# msq_ethrottle_soic.net
KiCad netlist of a schematic drawn in EasyEDA Pro
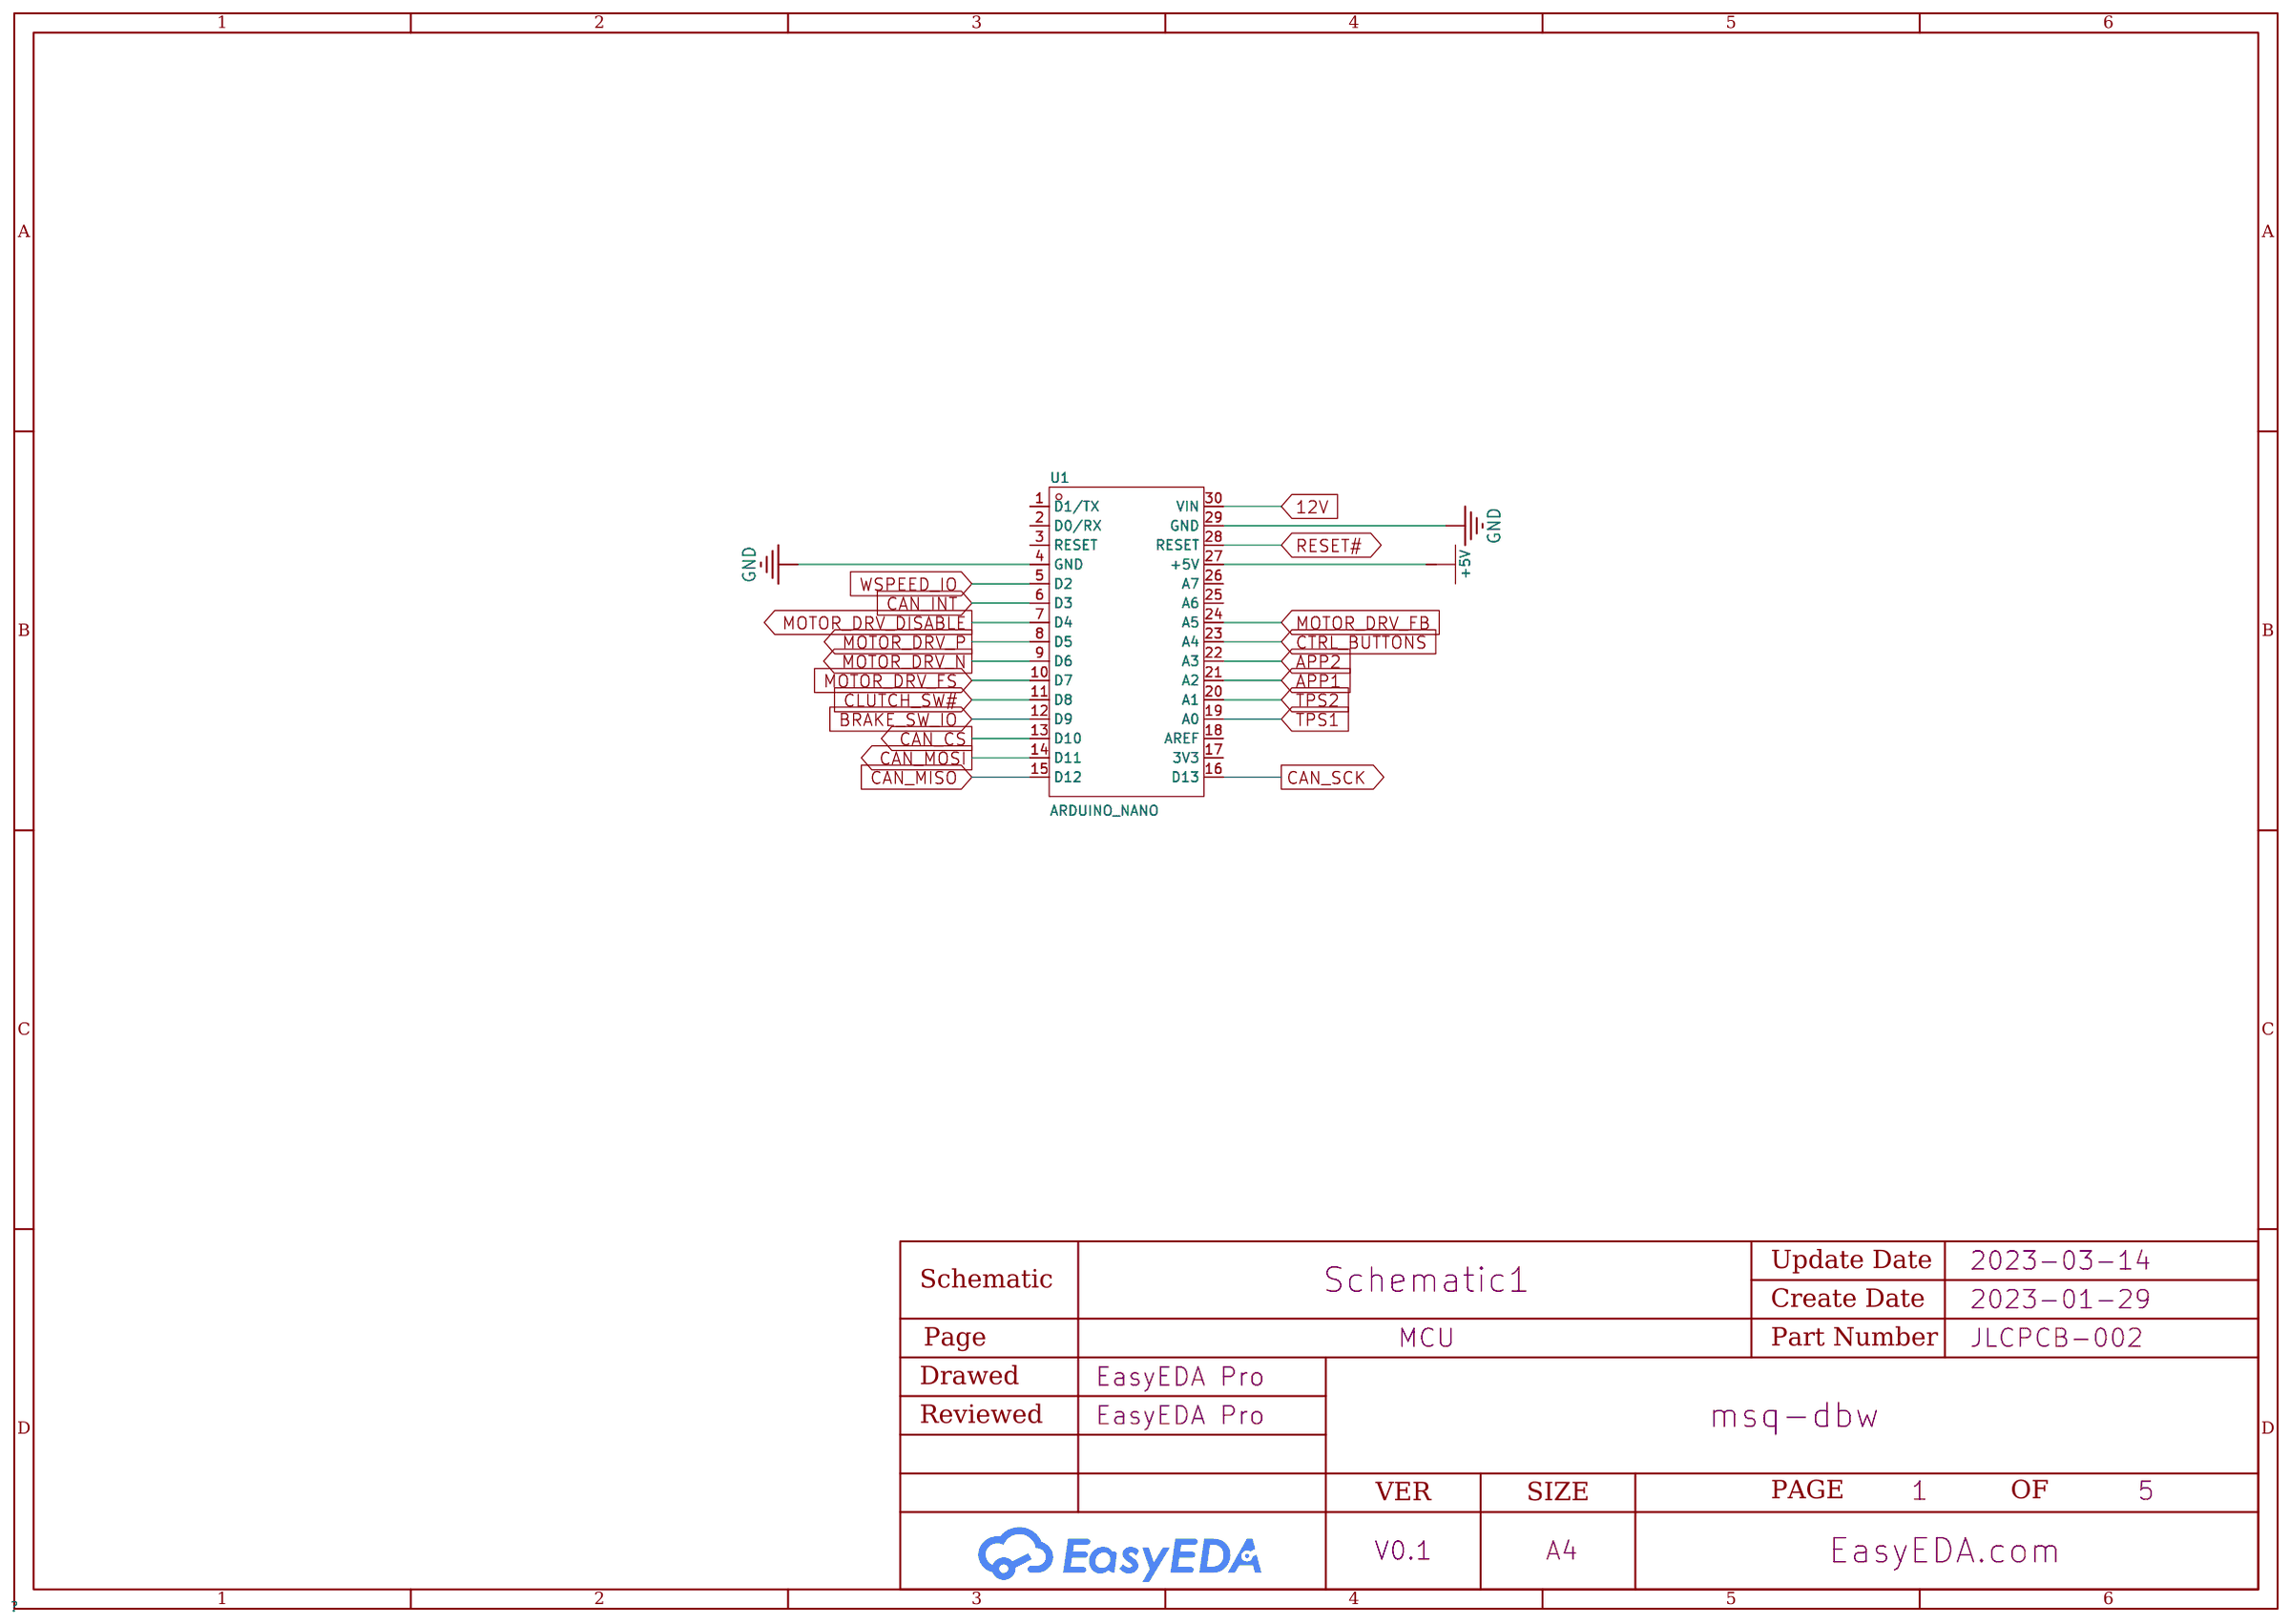
[diagram p0: MCU]
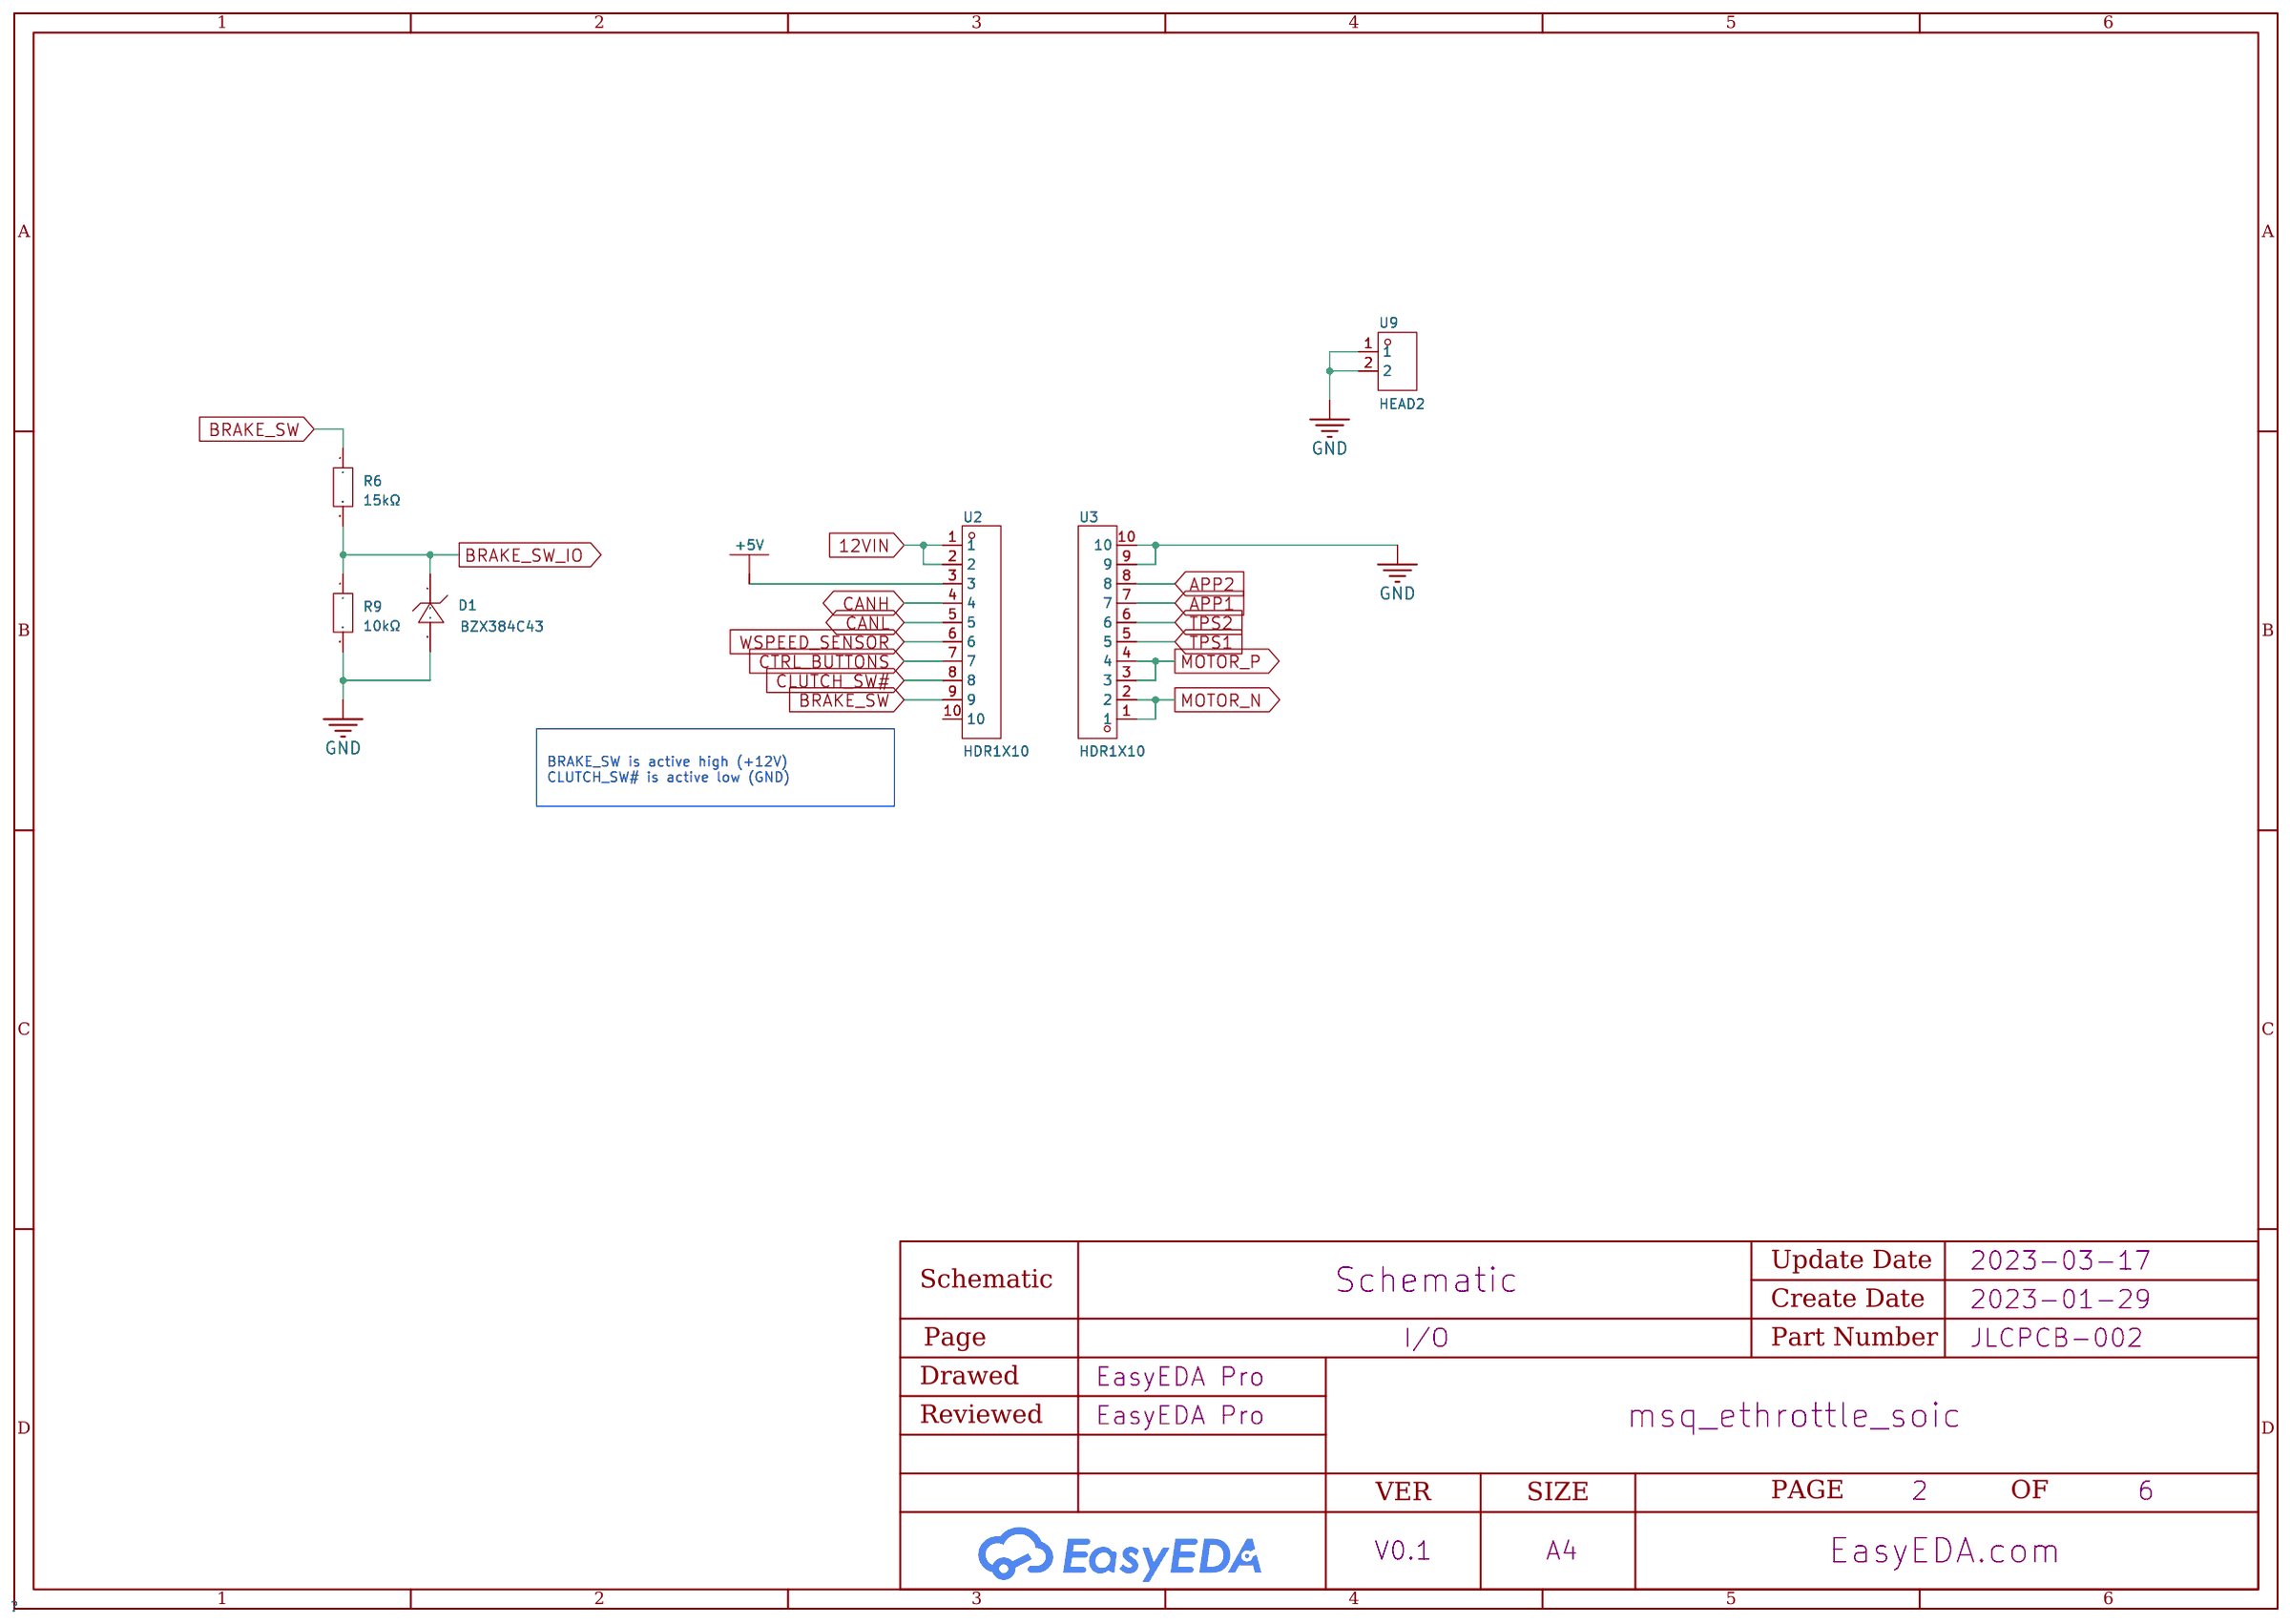
[diagram p1: I/O]
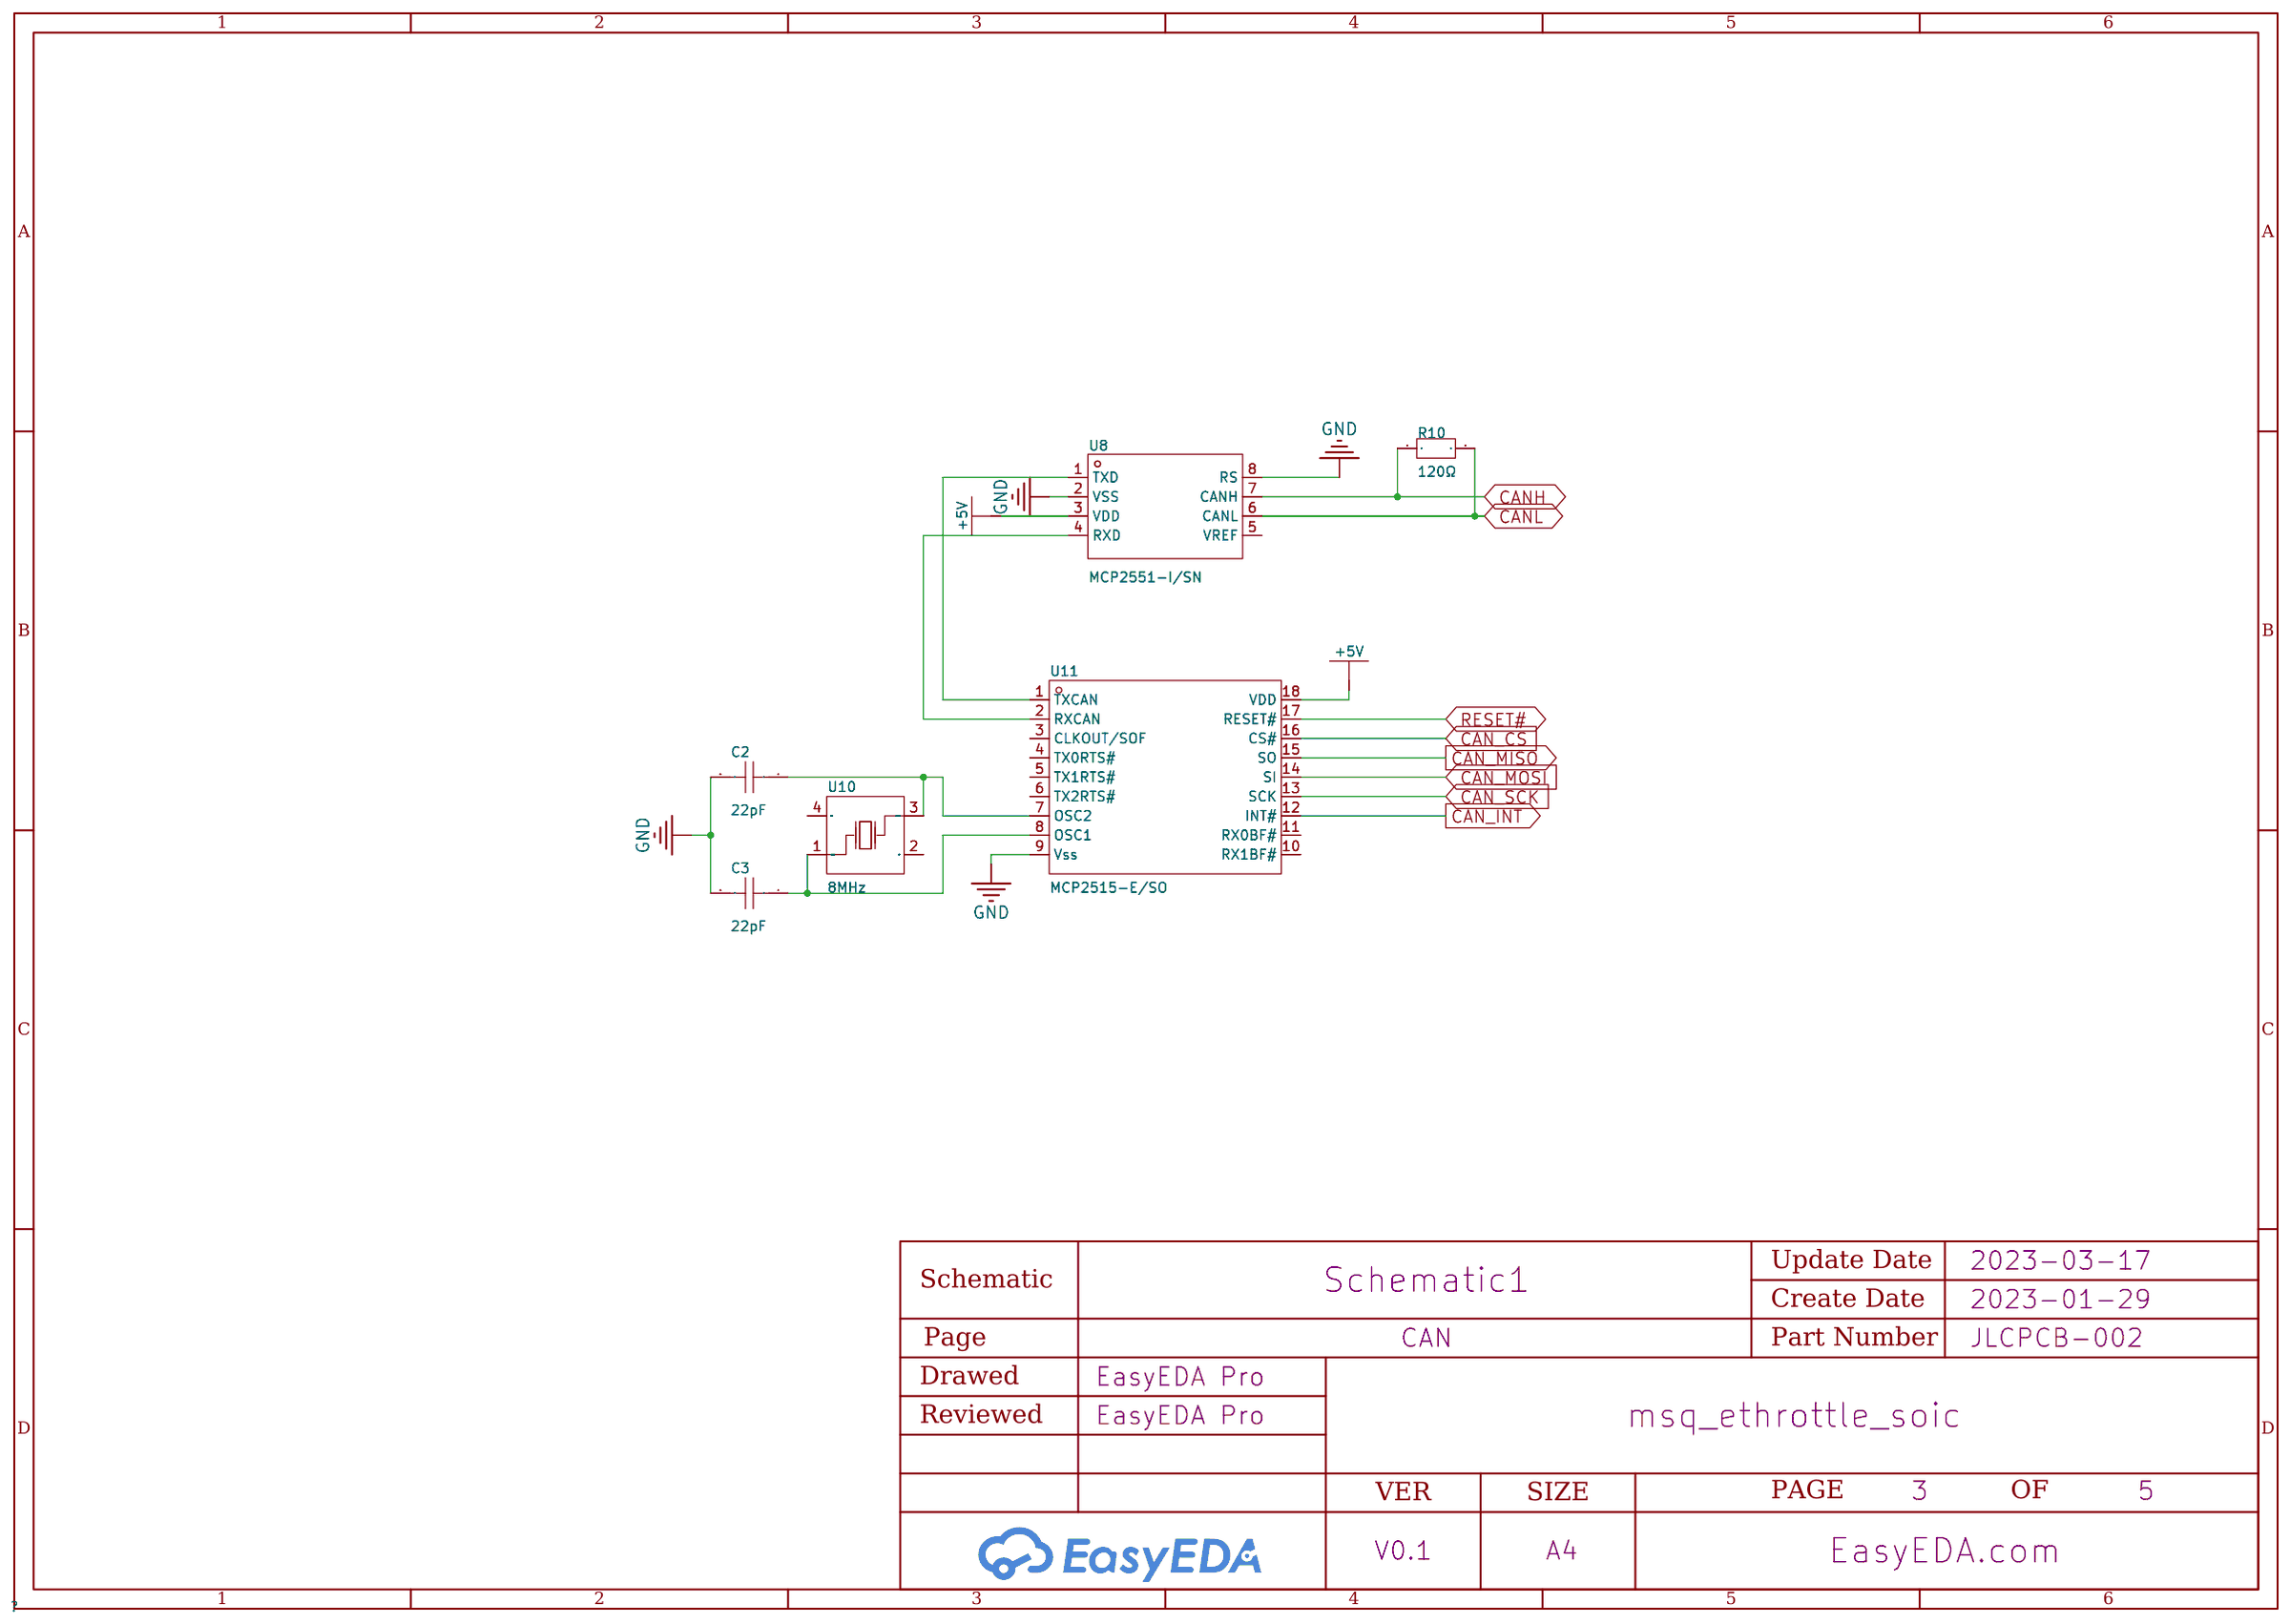
[diagram p2: CAN]
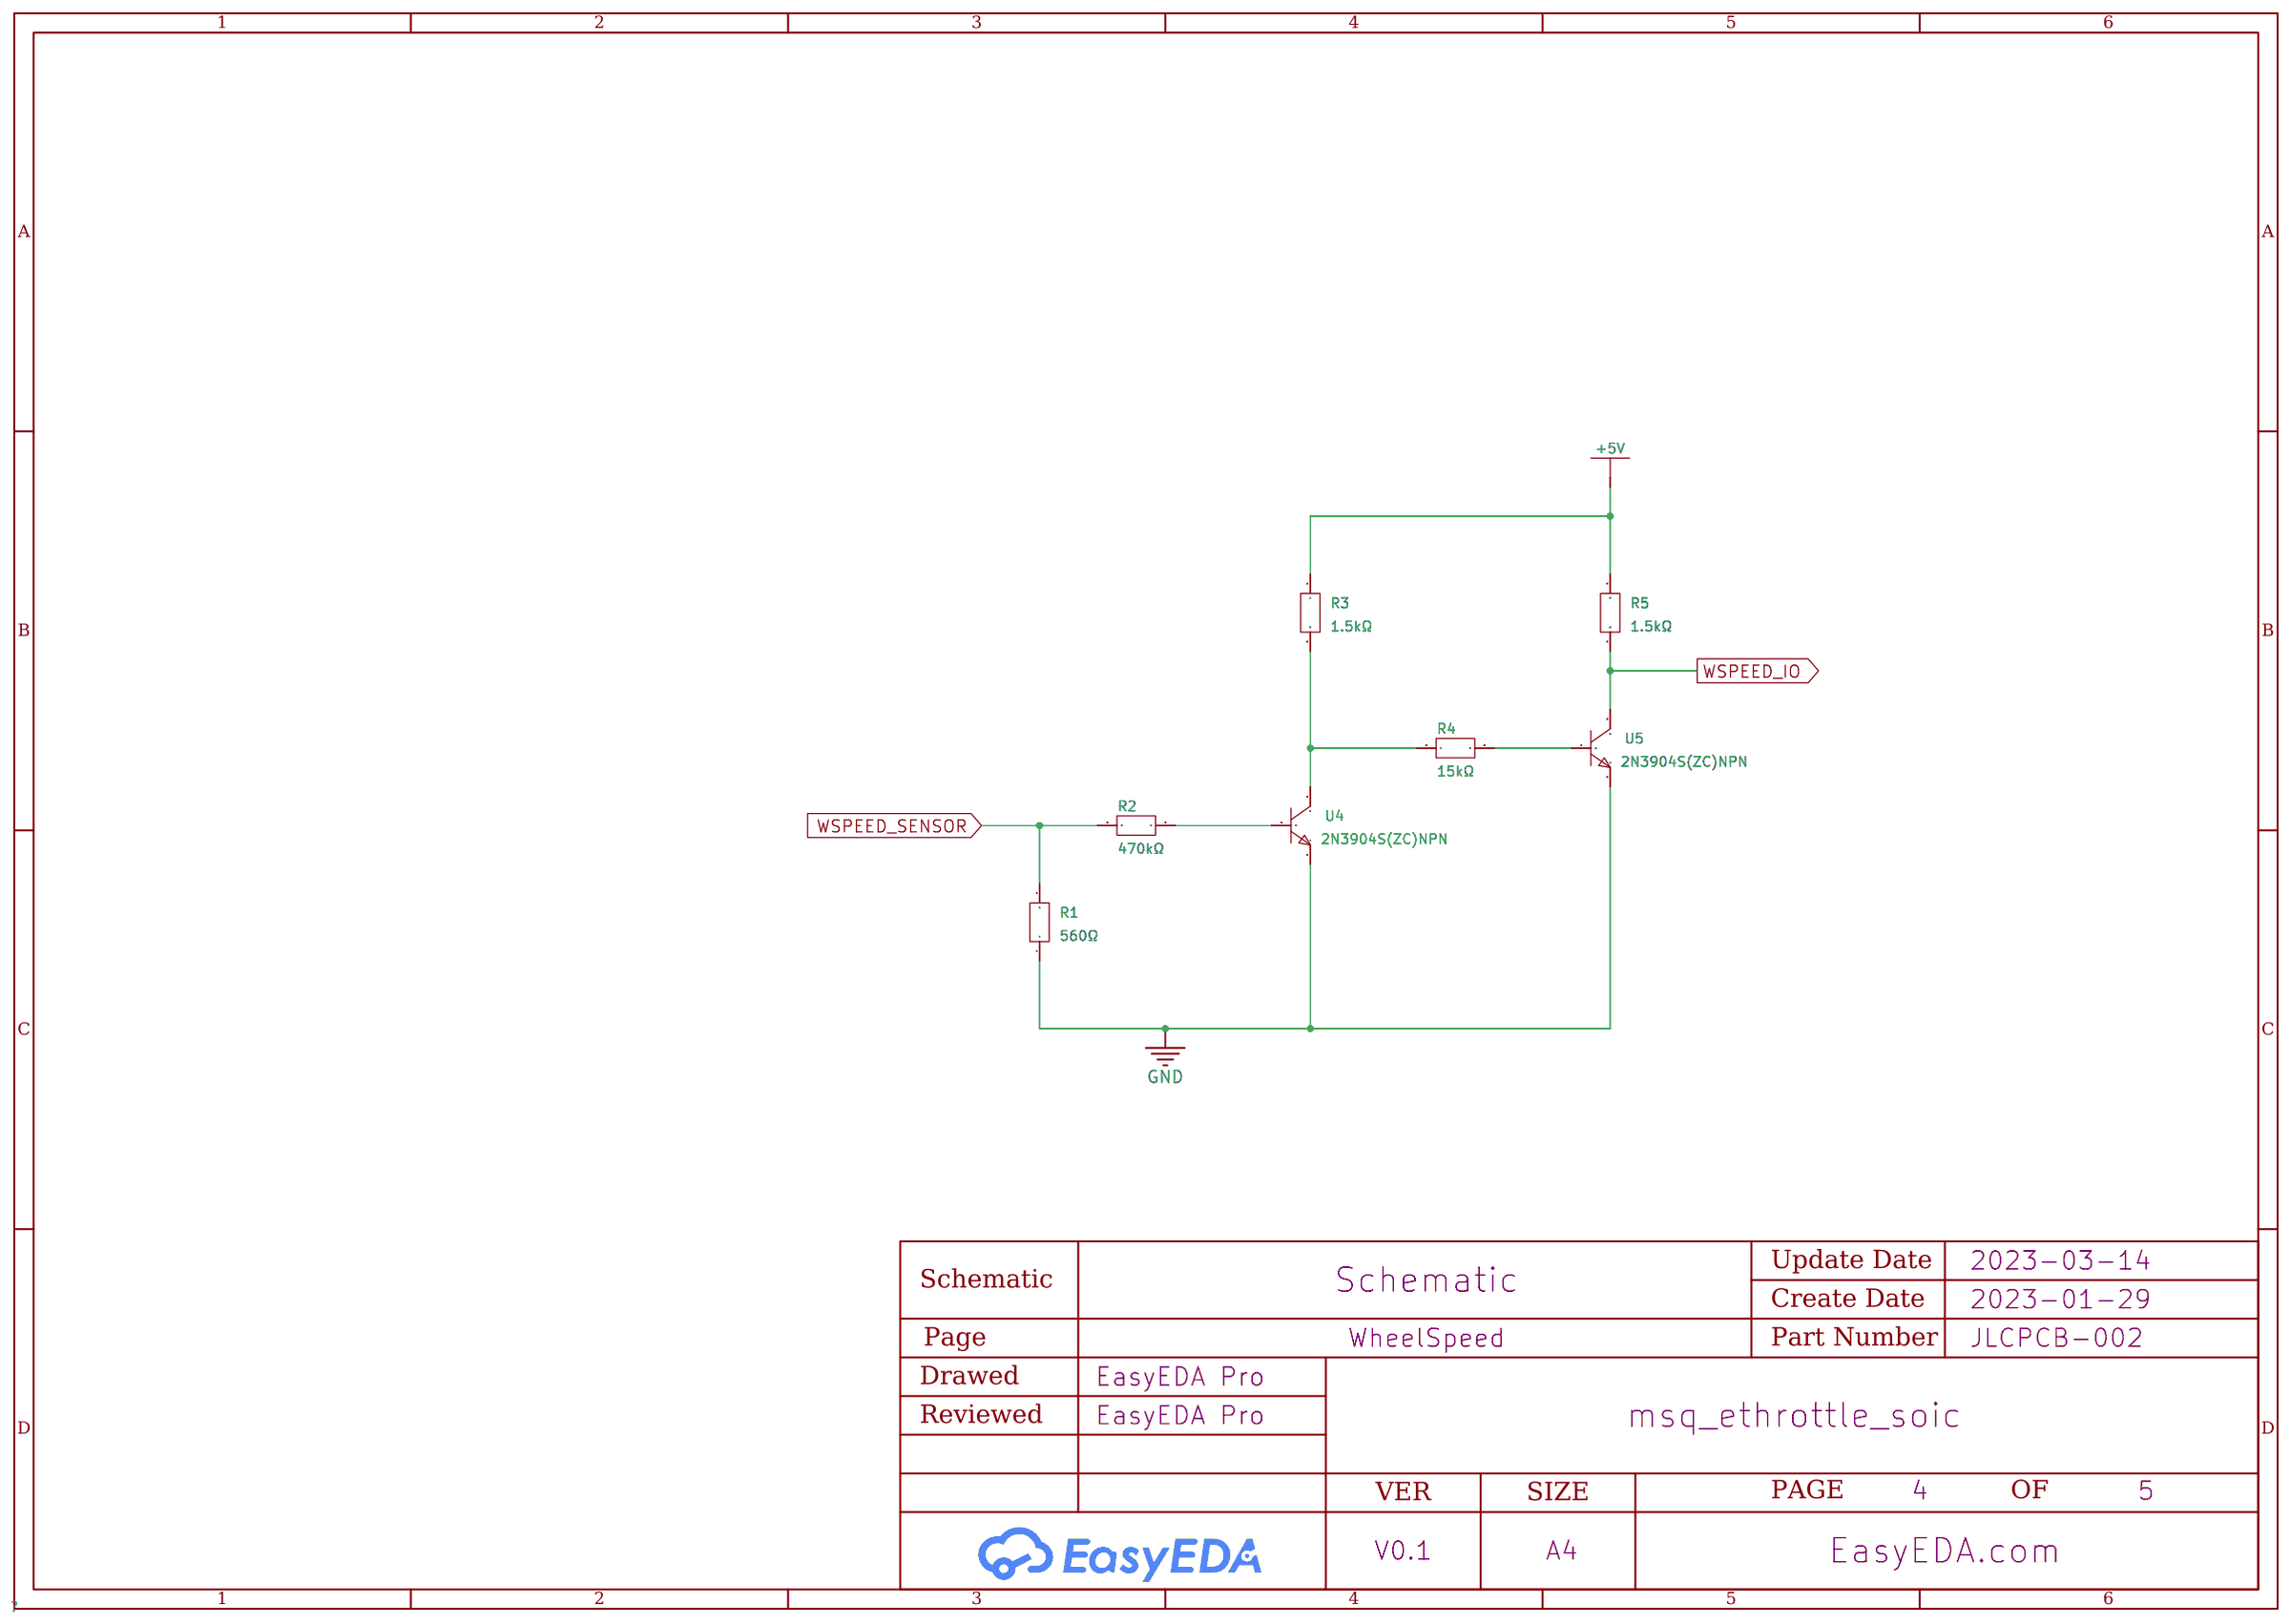
[diagram p3: WheelSpeed]
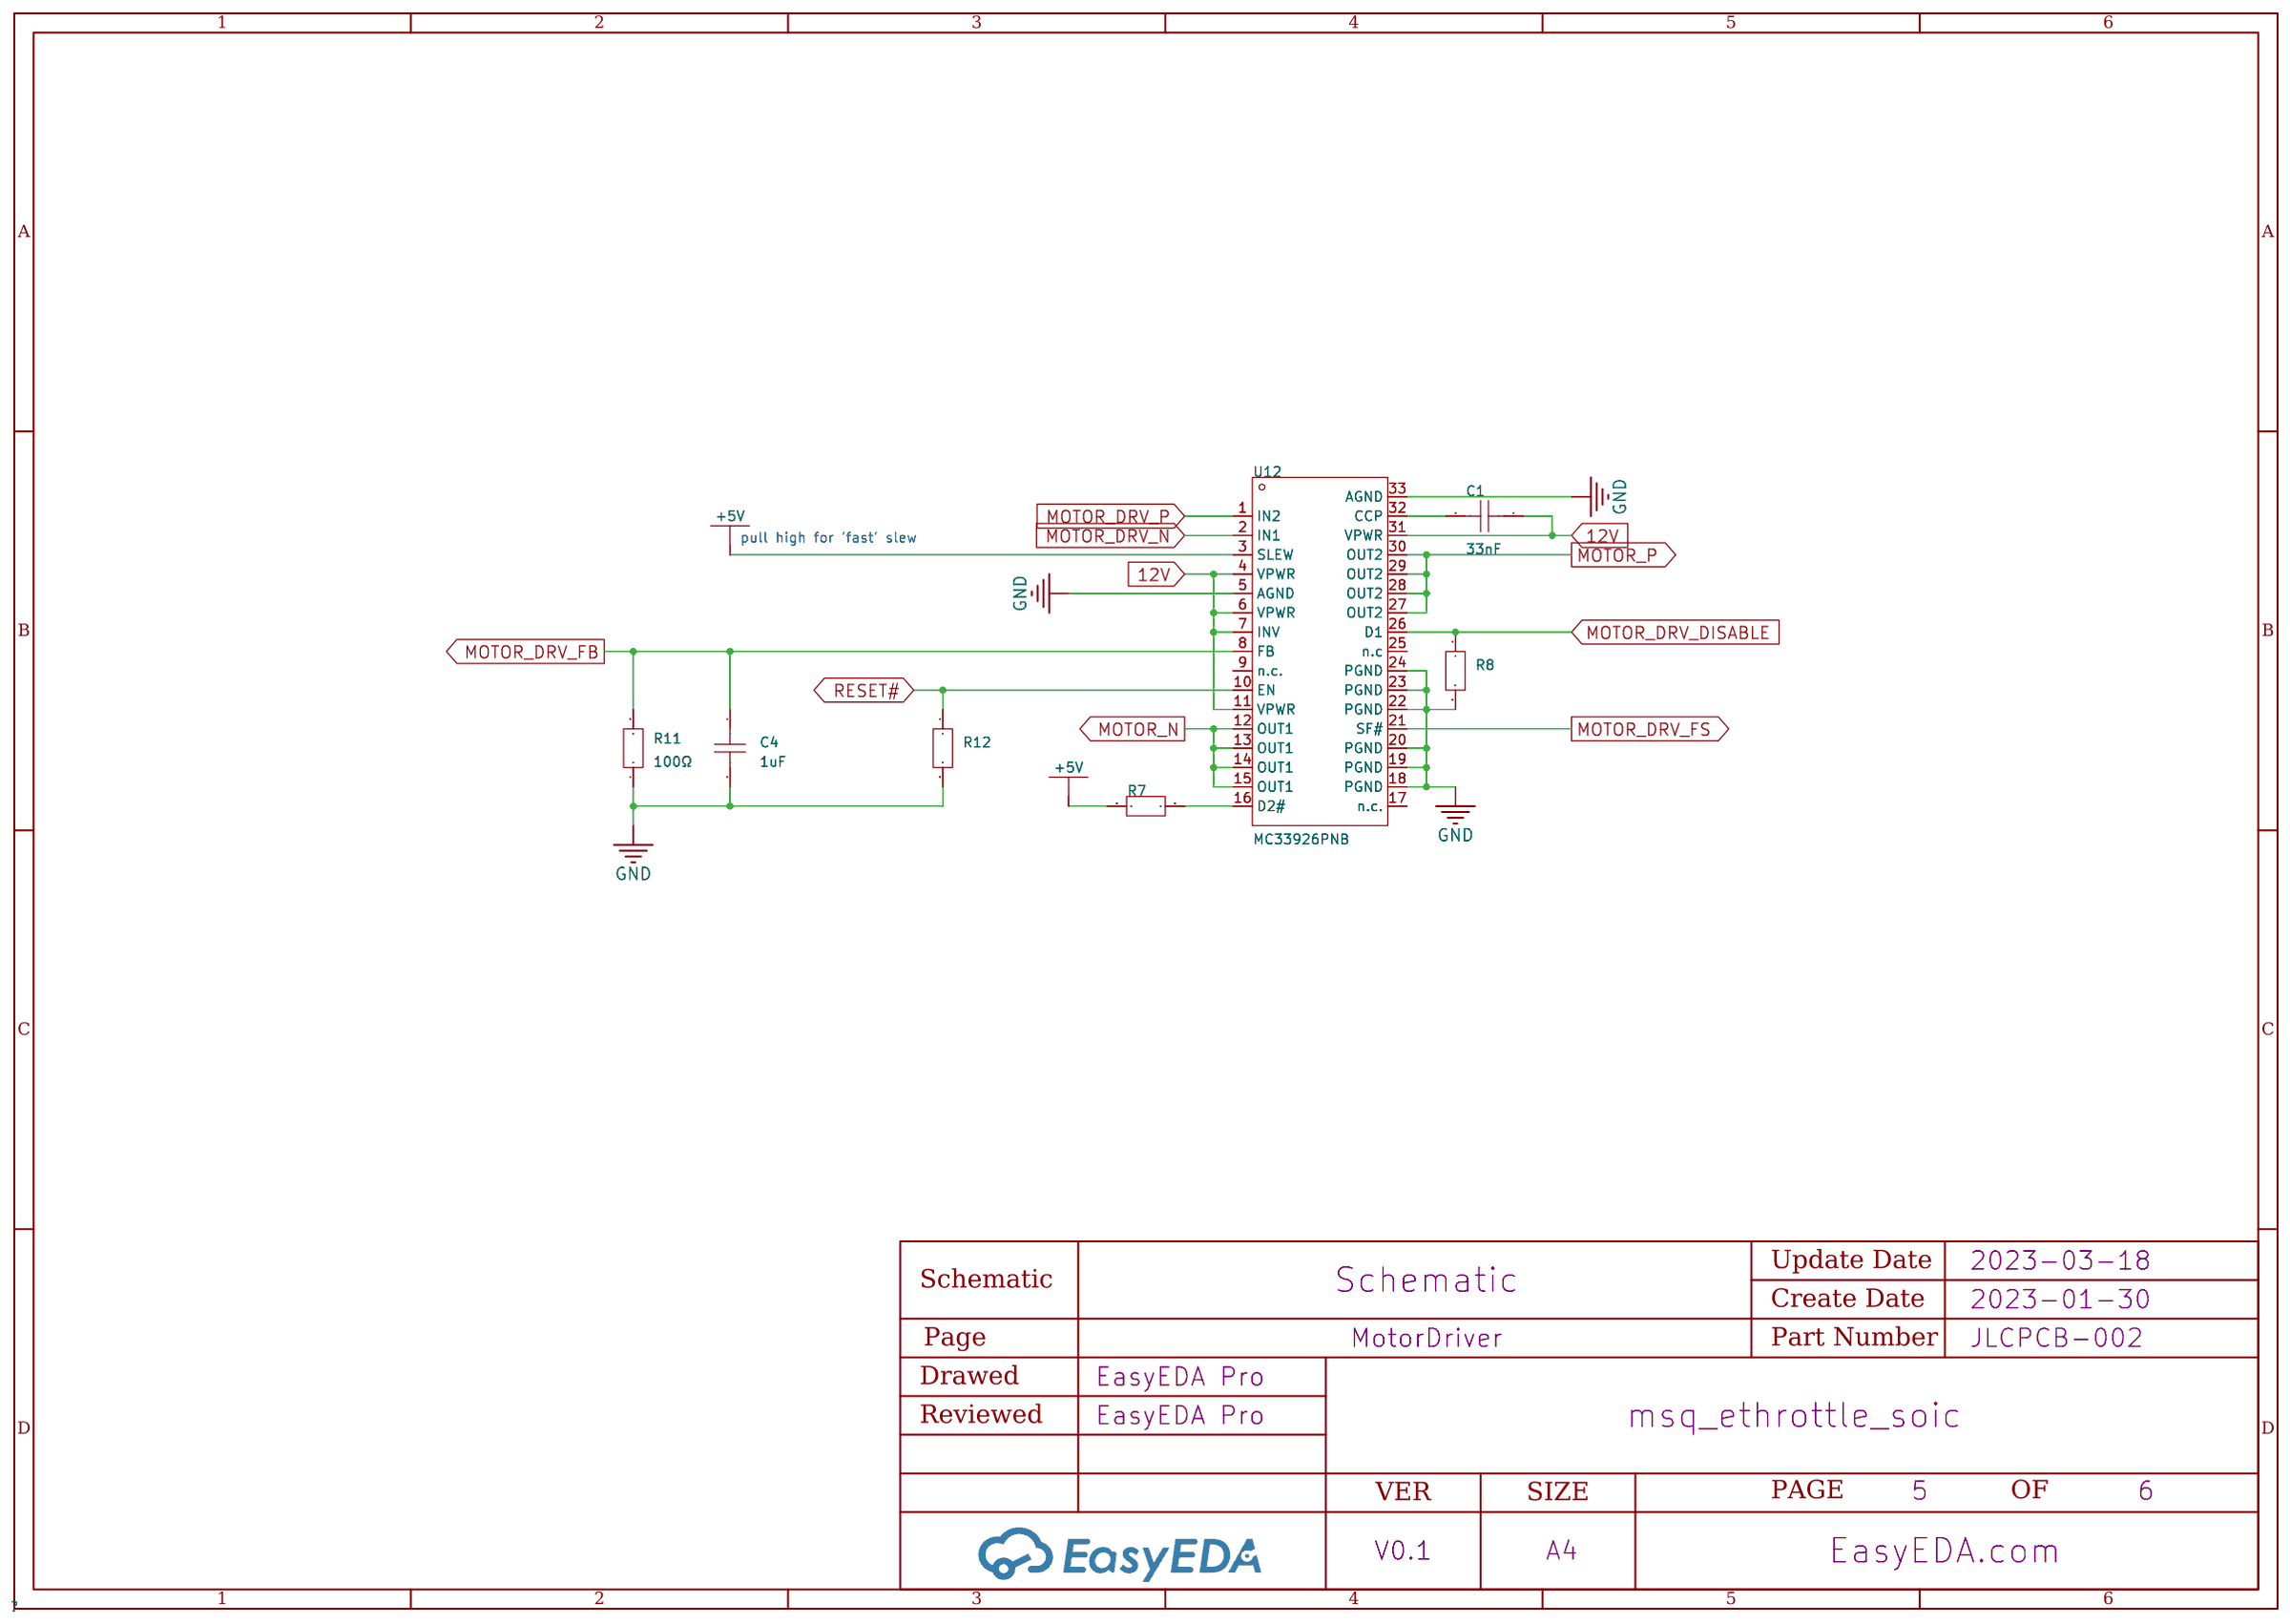
[diagram p4: MotorDriver]
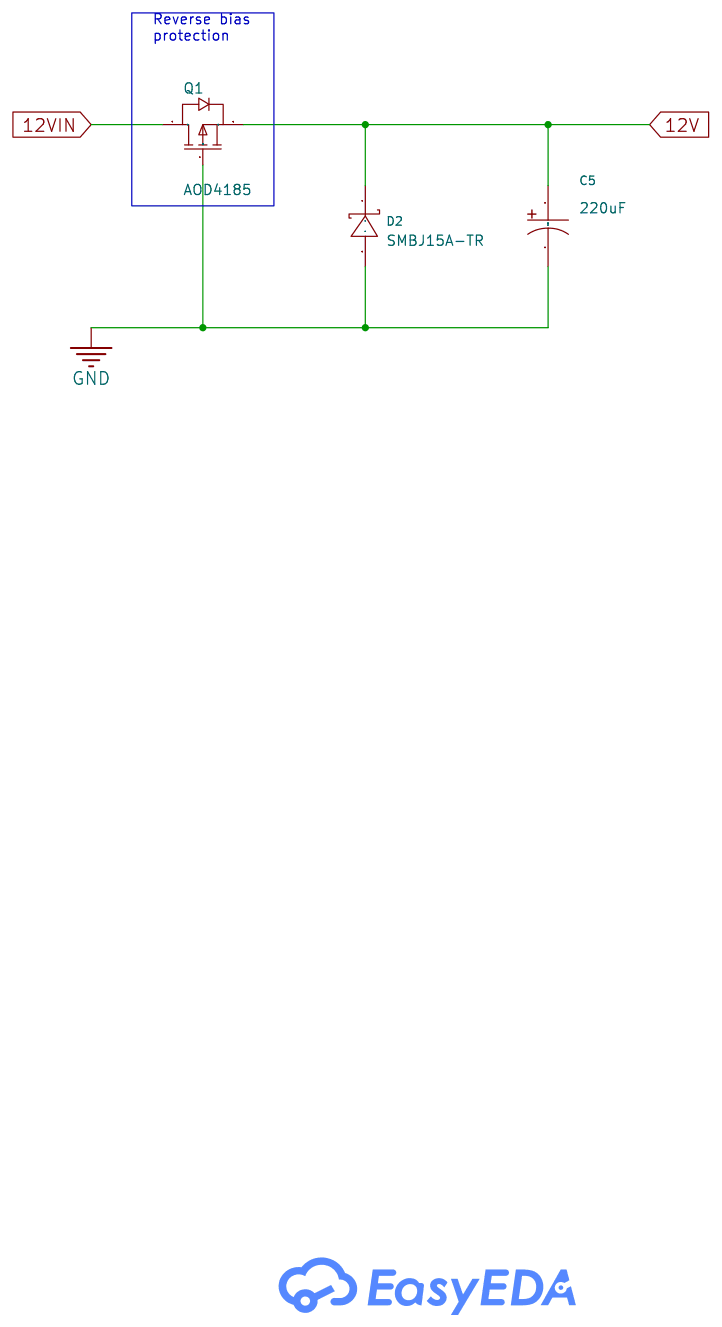
[diagram p5: Power]

(export (version "E")
  (design (tool "Eeschema 10.0.6"))
  (components
    (comp (ref "U1")
      (value "ARDUINO_NANO")
      (footprint "easyedapro:COMM-TH_ARDUINO_NANO")
      (libsource (lib "easyedapro") (part "ARDUINO_NANO"))
    )
    (comp (ref "D1")
      (value "BZX384C43")
      (footprint "easyedapro:SOD-323_L1.7-W1.3-LS2.6-RD")
      (fields (field (name "Manufacturer") "EIC"))
      (libsource (lib "easyedapro") (part "BZX384C43"))
    )
    (comp (ref "R6")
      (value "15kΩ")
      (footprint "easyedapro:R0805")
      (fields
        (field (name "Manufacturer Part") "0603WAF1002T5E")
        (field (name "Manufacturer") "UNI-ROYAL(厚声)")
      )
      (libsource (lib "easyedapro") (part "RT0805BRD07360RL"))
    )
    (comp (ref "R9")
      (value "10kΩ")
      (footprint "easyedapro:R0805")
      (fields
        (field (name "Manufacturer Part") "0603WAF1002T5E")
        (field (name "Manufacturer") "UNI-ROYAL(厚声)")
      )
      (libsource (lib "easyedapro") (part "RT0805BRD07360RL"))
    )
    (comp (ref "U2")
      (value "HDR1X10")
      (footprint "easyedapro:HDR-TH_10P-P2.54-V-F_C9900008052")
      (libsource (lib "easyedapro") (part "HDR1X10"))
    )
    (comp (ref "U3")
      (value "HDR1X10")
      (footprint "easyedapro:HDR-TH_10P-P2.54-V-F_C9900008052")
      (libsource (lib "easyedapro") (part "HDR1X10"))
    )
    (comp (ref "U9")
      (value "HEAD2")
      (footprint "easyedapro:HDR-TH_2P-P2.54-V-M")
      (libsource (lib "easyedapro") (part "HEAD2"))
    )
    (comp (ref "C2")
      (value "22pF")
      (footprint "easyedapro:C0603")
      (libsource (lib "easyedapro") (part "CAP"))
    )
    (comp (ref "C3")
      (value "22pF")
      (footprint "easyedapro:C0603")
      (libsource (lib "easyedapro") (part "CAP"))
    )
    (comp (ref "R10")
      (value "120Ω")
      (footprint "easyedapro:R0805")
      (fields
        (field (name "Manufacturer Part") "0603WAF1002T5E")
        (field (name "Manufacturer") "UNI-ROYAL(厚声)")
        (field (name "Tolerance") "±1%")
      )
      (libsource (lib "easyedapro") (part "RT0805BRD07360RL"))
    )
    (comp (ref "U8")
      (value "MCP2551-I/SN")
      (footprint "easyedapro:SOIC-8_L4.9-W3.9-P1.27-LS6.0-BL")
      (description "Type:Transceiver Supply Voltage:4.5V~5.5V Supply Voltage:4.5V~5.5V")
      (fields (field (name "Manufacturer") "MICROCHIP(美国微芯)"))
      (libsource (lib "easyedapro") (part "MCP2551-I/SN"))
    )
    (comp (ref "U10")
      (value "8MHz")
      (footprint "easyedapro:CRYSTAL-SMD_4P-L3.2-W2.5-BL")
      (fields (field (name "Manufacturer Part") "L327S270S11L") (field (name "Manufacturer") "Lucki(蓝晶)"))
      (libsource (lib "easyedapro") (part "L327S270S11L"))
    )
    (comp (ref "U11")
      (value "MCP2515-E/SO")
      (footprint "easyedapro:SOIC-18_L11.6-W7.5-P1.27-LS10.3-BL")
      (fields (field (name "Manufacturer") "MICROCHIP(美国微芯)"))
      (libsource (lib "easyedapro") (part "MCP2515-E/SO"))
    )
    (comp (ref "R1")
      (value "560Ω")
      (footprint "easyedapro:R0805")
      (fields
        (field (name "Manufacturer Part") "0603WAF1002T5E")
        (field (name "Manufacturer") "UNI-ROYAL(厚声)")
        (field (name "Tolerance") "±1%")
      )
      (libsource (lib "easyedapro") (part "RT0805BRD07360RL"))
    )
    (comp (ref "R2")
      (value "470kΩ")
      (footprint "easyedapro:R0805")
      (fields
        (field (name "Manufacturer Part") "0603WAF1002T5E")
        (field (name "Manufacturer") "UNI-ROYAL(厚声)")
        (field (name "Tolerance") "±1%")
      )
      (libsource (lib "easyedapro") (part "RT0805BRD07360RL"))
    )
    (comp (ref "R3")
      (value "1.5kΩ")
      (footprint "easyedapro:R0805")
      (fields
        (field (name "Manufacturer Part") "0603WAF1002T5E")
        (field (name "Manufacturer") "UNI-ROYAL(厚声)")
        (field (name "Tolerance") "±1%")
      )
      (libsource (lib "easyedapro") (part "RT0805BRD07360RL"))
    )
    (comp (ref "R4")
      (value "15kΩ")
      (footprint "easyedapro:R0805")
      (fields
        (field (name "Manufacturer Part") "0603WAF1002T5E")
        (field (name "Manufacturer") "UNI-ROYAL(厚声)")
        (field (name "Tolerance") "±1%")
      )
      (libsource (lib "easyedapro") (part "RT0805BRD07360RL"))
    )
    (comp (ref "R5")
      (value "1.5kΩ")
      (footprint "easyedapro:R0805")
      (fields
        (field (name "Manufacturer Part") "0603WAF1002T5E")
        (field (name "Manufacturer") "UNI-ROYAL(厚声)")
        (field (name "Tolerance") "±1%")
      )
      (libsource (lib "easyedapro") (part "RT0805BRD07360RL"))
    )
    (comp (ref "U4")
      (value "2N3904S(ZC)NPN")
      (footprint "easyedapro:SOT-23-3_L2.9-W1.3-P0.95-LS2.4-BR")
      (libsource (lib "easyedapro") (part "2N3904S(ZC)NPN"))
    )
    (comp (ref "U5")
      (value "2N3904S(ZC)NPN")
      (footprint "easyedapro:SOT-23-3_L2.9-W1.3-P0.95-LS2.4-BR")
      (libsource (lib "easyedapro") (part "2N3904S(ZC)NPN"))
    )
    (comp (ref "C1")
      (value "33nF")
      (footprint "easyedapro:C0603")
      (libsource (lib "easyedapro") (part "CAP"))
    )
    (comp (ref "C4") (value "1uF") (footprint "easyedapro:C0603") (libsource (lib "easyedapro") (part "CAP")))
    (comp (ref "R7")
      (value "10kΩ")
      (footprint "easyedapro:R0805")
      (fields
        (field (name "Manufacturer Part") "0603WAF1002T5E")
        (field (name "Manufacturer") "UNI-ROYAL(厚声)")
      )
      (libsource (lib "easyedapro") (part "RT0805BRD07360RL"))
    )
    (comp (ref "R8")
      (value "10kΩ")
      (footprint "easyedapro:R0805")
      (fields
        (field (name "Manufacturer Part") "0603WAF1002T5E")
        (field (name "Manufacturer") "UNI-ROYAL(厚声)")
      )
      (libsource (lib "easyedapro") (part "RT0805BRD07360RL"))
    )
    (comp (ref "R11")
      (value "100Ω")
      (footprint "easyedapro:R0805")
      (fields
        (field (name "Manufacturer Part") "0603WAF1002T5E")
        (field (name "Manufacturer") "UNI-ROYAL(厚声)")
      )
      (libsource (lib "easyedapro") (part "RT0805BRD07360RL"))
    )
    (comp (ref "R12")
      (value "10kΩ")
      (footprint "easyedapro:R0805")
      (fields
        (field (name "Manufacturer Part") "0603WAF1002T5E")
        (field (name "Manufacturer") "UNI-ROYAL(厚声)")
      )
      (libsource (lib "easyedapro") (part "RT0805BRD07360RL"))
    )
    (comp (ref "U12")
      (value "MC33926PNB")
      (footprint "easyedapro:PQFN-32_L8.0-W8.0-P0.80-TL-EP5.0")
      (fields (field (name "Manufacturer") "NXP(恩智浦)"))
      (libsource (lib "easyedapro") (part "MC33926PNB"))
    )
    (comp (ref "C5")
      (value "220uF")
      (footprint "easyedapro:CAP-SMD_BD6.3-L6.6-W6.6-FD")
      (fields (field (name "Manufacturer Part") "EEEFTE221XAP") (field (name "Manufacturer") "PANASONIC(松下)"))
      (libsource (lib "easyedapro") (part "EEEFTE221XAP"))
    )
    (comp (ref "D2")
      (value "SMBJ15A-TR")
      (footprint "easyedapro:SMB_L4.6-W3.6-LS5.3-RD")
      (fields (field (name "Manufacturer") "ST(意法半导体)"))
      (libsource (lib "easyedapro") (part "SMBJ15A-TR"))
    )
    (comp (ref "Q1")
      (value "AOD4185")
      (footprint "easyedapro:TO-252-3_L6.6-W6.1-P4.57-LS9.9-BR-CW")
      (fields (field (name "Manufacturer") "AOS"))
      (libsource (lib "easyedapro") (part "AOD4185_C400894"))
    )
  )
  (nets
    (net (code "1") (name "+5V") (class "Default")
      (node (ref "R3") (pin "1") (pinfunction "1_1") (pintype "input"))
      (node (ref "R5") (pin "2") (pinfunction "2_2") (pintype "input"))
      (node (ref "R7") (pin "2") (pinfunction "2_2") (pintype "input"))
      (node (ref "U1") (pin "27") (pinfunction "+5V_27") (pintype "input"))
      (node (ref "U11") (pin "18") (pinfunction "VDD_18") (pintype "input"))
      (node (ref "U12") (pin "3") (pinfunction "SLEW_3") (pintype "unspecified"))
      (node (ref "U2") (pin "3") (pinfunction "3_3") (pintype "input"))
      (node (ref "U8") (pin "3") (pinfunction "VDD_3") (pintype "input"))
    )
    (net (code "2") (name "12V") (class "Default")
      (node (ref "C1") (pin "1") (pinfunction "1_1") (pintype "input"))
      (node (ref "C5") (pin "1") (pinfunction "1_1") (pintype "input"))
      (node (ref "D2") (pin "1") (pinfunction "K_1") (pintype "input"))
      (node (ref "Q1") (pin "3") (pinfunction "S_3") (pintype "unspecified"))
      (node (ref "U1") (pin "30") (pinfunction "VIN_30") (pintype "input"))
      (node (ref "U12") (pin "11") (pinfunction "VPWR_11") (pintype "unspecified"))
      (node (ref "U12") (pin "31") (pinfunction "VPWR_31") (pintype "unspecified"))
      (node (ref "U12") (pin "4") (pinfunction "VPWR_4") (pintype "unspecified"))
      (node (ref "U12") (pin "6") (pinfunction "VPWR_6") (pintype "unspecified"))
      (node (ref "U12") (pin "7") (pinfunction "INV_7") (pintype "unspecified"))
    )
    (net (code "3") (name "12VIN") (class "Default")
      (node (ref "Q1") (pin "2") (pinfunction "D_2") (pintype "unspecified"))
      (node (ref "U2") (pin "1") (pinfunction "1_1") (pintype "input"))
      (node (ref "U2") (pin "2") (pinfunction "2_2") (pintype "input"))
    )
    (net (code "4") (name "APP1") (class "Default")
      (node (ref "U1") (pin "21") (pinfunction "A2_21") (pintype "input"))
      (node (ref "U3") (pin "7") (pinfunction "7_7") (pintype "input"))
    )
    (net (code "5") (name "APP2") (class "Default")
      (node (ref "U1") (pin "22") (pinfunction "A3_22") (pintype "input"))
      (node (ref "U3") (pin "8") (pinfunction "8_8") (pintype "input"))
    )
    (net (code "6") (name "BRAKE_SW") (class "Default")
      (node (ref "R6") (pin "1") (pinfunction "1_1") (pintype "input"))
      (node (ref "U2") (pin "9") (pinfunction "9_9") (pintype "input"))
    )
    (net (code "7") (name "BRAKE_SW_IO") (class "Default")
      (node (ref "D1") (pin "1") (pinfunction "C_1") (pintype "input"))
      (node (ref "R6") (pin "2") (pinfunction "2_2") (pintype "input"))
      (node (ref "R9") (pin "1") (pinfunction "1_1") (pintype "input"))
      (node (ref "U1") (pin "12") (pinfunction "D9_12") (pintype "input"))
    )
    (net (code "8") (name "CANH") (class "Default")
      (node (ref "R10") (pin "1") (pinfunction "1_1") (pintype "input"))
      (node (ref "U2") (pin "4") (pinfunction "4_4") (pintype "input"))
      (node (ref "U8") (pin "7") (pinfunction "CANH_7") (pintype "input"))
    )
    (net (code "9") (name "CANL") (class "Default")
      (node (ref "R10") (pin "2") (pinfunction "2_2") (pintype "input"))
      (node (ref "U2") (pin "5") (pinfunction "5_5") (pintype "input"))
      (node (ref "U8") (pin "6") (pinfunction "CANL_6") (pintype "input"))
    )
    (net (code "10") (name "CAN_CS") (class "Default")
      (node (ref "U1") (pin "13") (pinfunction "D10_13") (pintype "input"))
      (node (ref "U11") (pin "16") (pinfunction "CS#_16") (pintype "input"))
    )
    (net (code "11") (name "CAN_INT") (class "Default")
      (node (ref "U1") (pin "6") (pinfunction "D3_6") (pintype "input"))
      (node (ref "U11") (pin "12") (pinfunction "INT#_12") (pintype "input"))
    )
    (net (code "12") (name "CAN_MISO") (class "Default")
      (node (ref "U1") (pin "15") (pinfunction "D12_15") (pintype "input"))
      (node (ref "U11") (pin "15") (pinfunction "SO_15") (pintype "input"))
    )
    (net (code "13") (name "CAN_MOSI") (class "Default")
      (node (ref "U1") (pin "14") (pinfunction "D11_14") (pintype "input"))
      (node (ref "U11") (pin "14") (pinfunction "SI_14") (pintype "input"))
    )
    (net (code "14") (name "CAN_SCK") (class "Default")
      (node (ref "U1") (pin "16") (pinfunction "D13_16") (pintype "input"))
      (node (ref "U11") (pin "13") (pinfunction "SCK_13") (pintype "input"))
    )
    (net (code "15") (name "CLUTCH_SW#") (class "Default")
      (node (ref "U1") (pin "11") (pinfunction "D8_11") (pintype "input"))
      (node (ref "U2") (pin "8") (pinfunction "8_8") (pintype "input"))
    )
    (net (code "16") (name "CTRL_BUTTONS") (class "Default")
      (node (ref "U1") (pin "23") (pinfunction "A4_23") (pintype "input"))
      (node (ref "U2") (pin "7") (pinfunction "7_7") (pintype "input"))
    )
    (net (code "17") (name "GND") (class "Default")
      (node (ref "C2") (pin "2") (pinfunction "2_2") (pintype "input"))
      (node (ref "C3") (pin "2") (pinfunction "2_2") (pintype "input"))
      (node (ref "C4") (pin "2") (pinfunction "2_2") (pintype "input"))
      (node (ref "C5") (pin "2") (pinfunction "2_2") (pintype "input"))
      (node (ref "D1") (pin "2") (pinfunction "A_2") (pintype "input"))
      (node (ref "D2") (pin "2") (pinfunction "A_2") (pintype "input"))
      (node (ref "Q1") (pin "1") (pinfunction "G_1") (pintype "unspecified"))
      (node (ref "R1") (pin "1") (pinfunction "1_1") (pintype "input"))
      (node (ref "R11") (pin "1") (pinfunction "1_1") (pintype "input"))
      (node (ref "R12") (pin "2") (pinfunction "2_2") (pintype "input"))
      (node (ref "R8") (pin "2") (pinfunction "2_2") (pintype "input"))
      (node (ref "R9") (pin "2") (pinfunction "2_2") (pintype "input"))
      (node (ref "U1") (pin "29") (pinfunction "GND_29") (pintype "input"))
      (node (ref "U1") (pin "4") (pinfunction "GND_4") (pintype "input"))
      (node (ref "U11") (pin "9") (pinfunction "Vss_9") (pintype "input"))
      (node (ref "U12") (pin "18") (pinfunction "PGND_18") (pintype "unspecified"))
      (node (ref "U12") (pin "19") (pinfunction "PGND_19") (pintype "unspecified"))
      (node (ref "U12") (pin "20") (pinfunction "PGND_20") (pintype "unspecified"))
      (node (ref "U12") (pin "22") (pinfunction "PGND_22") (pintype "unspecified"))
      (node (ref "U12") (pin "23") (pinfunction "PGND_23") (pintype "unspecified"))
      (node (ref "U12") (pin "24") (pinfunction "PGND_24") (pintype "unspecified"))
      (node (ref "U12") (pin "33") (pinfunction "AGND_33") (pintype "unspecified"))
      (node (ref "U12") (pin "5") (pinfunction "AGND_5") (pintype "unspecified"))
      (node (ref "U3") (pin "10") (pinfunction "10_10") (pintype "input"))
      (node (ref "U3") (pin "9") (pinfunction "9_9") (pintype "input"))
      (node (ref "U4") (pin "2") (pinfunction "E_2") (pintype "input"))
      (node (ref "U5") (pin "2") (pinfunction "E_2") (pintype "input"))
      (node (ref "U8") (pin "2") (pinfunction "VSS_2") (pintype "input"))
      (node (ref "U8") (pin "8") (pinfunction "RS_8") (pintype "input"))
      (node (ref "U9") (pin "1") (pinfunction "1_1") (pintype "input"))
      (node (ref "U9") (pin "2") (pinfunction "2_2") (pintype "input"))
    )
    (net (code "18") (name "MOTOR_DRV_DISABLE") (class "Default")
      (node (ref "R8") (pin "1") (pinfunction "1_1") (pintype "input"))
      (node (ref "U1") (pin "7") (pinfunction "D4_7") (pintype "input"))
      (node (ref "U12") (pin "26") (pinfunction "D1_26") (pintype "unspecified"))
    )
    (net (code "19") (name "MOTOR_DRV_FB") (class "Default")
      (node (ref "C4") (pin "1") (pinfunction "1_1") (pintype "input"))
      (node (ref "R11") (pin "2") (pinfunction "2_2") (pintype "input"))
      (node (ref "U1") (pin "24") (pinfunction "A5_24") (pintype "input"))
      (node (ref "U12") (pin "8") (pinfunction "FB_8") (pintype "unspecified"))
    )
    (net (code "20") (name "MOTOR_DRV_FS") (class "Default")
      (node (ref "U1") (pin "10") (pinfunction "D7_10") (pintype "input"))
      (node (ref "U12") (pin "21") (pinfunction "SF#_21") (pintype "unspecified"))
    )
    (net (code "21") (name "MOTOR_DRV_N") (class "Default")
      (node (ref "U1") (pin "9") (pinfunction "D6_9") (pintype "input"))
      (node (ref "U12") (pin "2") (pinfunction "IN1_2") (pintype "unspecified"))
    )
    (net (code "22") (name "MOTOR_DRV_P") (class "Default")
      (node (ref "U1") (pin "8") (pinfunction "D5_8") (pintype "input"))
      (node (ref "U12") (pin "1") (pinfunction "IN2_1") (pintype "unspecified"))
    )
    (net (code "23") (name "MOTOR_N") (class "Default")
      (node (ref "U12") (pin "12") (pinfunction "OUT1_12") (pintype "unspecified"))
      (node (ref "U12") (pin "13") (pinfunction "OUT1_13") (pintype "unspecified"))
      (node (ref "U12") (pin "14") (pinfunction "OUT1_14") (pintype "unspecified"))
      (node (ref "U12") (pin "15") (pinfunction "OUT1_15") (pintype "unspecified"))
      (node (ref "U3") (pin "1") (pinfunction "1_1") (pintype "input"))
      (node (ref "U3") (pin "2") (pinfunction "2_2") (pintype "input"))
    )
    (net (code "24") (name "MOTOR_P") (class "Default")
      (node (ref "U12") (pin "27") (pinfunction "OUT2_27") (pintype "unspecified"))
      (node (ref "U12") (pin "28") (pinfunction "OUT2_28") (pintype "unspecified"))
      (node (ref "U12") (pin "29") (pinfunction "OUT2_29") (pintype "unspecified"))
      (node (ref "U12") (pin "30") (pinfunction "OUT2_30") (pintype "unspecified"))
      (node (ref "U3") (pin "3") (pinfunction "3_3") (pintype "input"))
      (node (ref "U3") (pin "4") (pinfunction "4_4") (pintype "input"))
    )
    (net (code "25") (name "Net-(U4-B)") (class "Default")
      (node (ref "R2") (pin "1") (pinfunction "1_1") (pintype "input"))
      (node (ref "U4") (pin "1") (pinfunction "B_1") (pintype "input"))
    )
    (net (code "26") (name "Net-(U4-C)") (class "Default")
      (node (ref "R3") (pin "2") (pinfunction "2_2") (pintype "input"))
      (node (ref "R4") (pin "1") (pinfunction "1_1") (pintype "input"))
      (node (ref "U4") (pin "3") (pinfunction "C_3") (pintype "input"))
    )
    (net (code "27") (name "Net-(U5-B)") (class "Default")
      (node (ref "R4") (pin "2") (pinfunction "2_2") (pintype "input"))
      (node (ref "U5") (pin "1") (pinfunction "B_1") (pintype "input"))
    )
    (net (code "28") (name "Net-(U10-Xtal_Terminal_(Input))") (class "Default")
      (node (ref "C3") (pin "1") (pinfunction "1_1") (pintype "input"))
      (node (ref "U10") (pin "1") (pinfunction "Xtal_Terminal_(Input)_1") (pintype "input"))
      (node (ref "U11") (pin "8") (pinfunction "OSC1_8") (pintype "input"))
    )
    (net (code "29") (name "Net-(U10-Xtal_Terminal_(Output))") (class "Default")
      (node (ref "C2") (pin "1") (pinfunction "1_1") (pintype "input"))
      (node (ref "U10") (pin "3") (pinfunction "Xtal_Terminal_(Output)_3") (pintype "input"))
      (node (ref "U11") (pin "7") (pinfunction "OSC2_7") (pintype "input"))
    )
    (net (code "30") (name "Net-(U11-RXCAN)") (class "Default")
      (node (ref "U11") (pin "2") (pinfunction "RXCAN_2") (pintype "input"))
      (node (ref "U8") (pin "4") (pinfunction "RXD_4") (pintype "input"))
    )
    (net (code "31") (name "Net-(U11-TXCAN)") (class "Default")
      (node (ref "U11") (pin "1") (pinfunction "TXCAN_1") (pintype "input"))
      (node (ref "U8") (pin "1") (pinfunction "TXD_1") (pintype "input"))
    )
    (net (code "32") (name "Net-(U12-CCP)") (class "Default")
      (node (ref "C1") (pin "2") (pinfunction "2_2") (pintype "input"))
      (node (ref "U12") (pin "32") (pinfunction "CCP_32") (pintype "unspecified"))
    )
    (net (code "33") (name "Net-(U12-D2#)") (class "Default")
      (node (ref "R7") (pin "1") (pinfunction "1_1") (pintype "input"))
      (node (ref "U12") (pin "16") (pinfunction "D2#_16") (pintype "unspecified"))
    )
    (net (code "34") (name "RESET#") (class "Default")
      (node (ref "R12") (pin "1") (pinfunction "1_1") (pintype "input"))
      (node (ref "U1") (pin "28") (pinfunction "RESET_28") (pintype "input"))
      (node (ref "U11") (pin "17") (pinfunction "RESET#_17") (pintype "input"))
      (node (ref "U12") (pin "10") (pinfunction "EN_10") (pintype "unspecified"))
    )
    (net (code "35") (name "TPS1") (class "Default")
      (node (ref "U1") (pin "19") (pinfunction "A0_19") (pintype "input"))
      (node (ref "U3") (pin "5") (pinfunction "5_5") (pintype "input"))
    )
    (net (code "36") (name "TPS2") (class "Default")
      (node (ref "U1") (pin "20") (pinfunction "A1_20") (pintype "input"))
      (node (ref "U3") (pin "6") (pinfunction "6_6") (pintype "input"))
    )
    (net (code "37") (name "WSPEED_IO") (class "Default")
      (node (ref "R5") (pin "1") (pinfunction "1_1") (pintype "input"))
      (node (ref "U1") (pin "5") (pinfunction "D2_5") (pintype "input"))
      (node (ref "U5") (pin "3") (pinfunction "C_3") (pintype "input"))
    )
    (net (code "38") (name "WSPEED_SENSOR") (class "Default")
      (node (ref "R1") (pin "2") (pinfunction "2_2") (pintype "input"))
      (node (ref "R2") (pin "2") (pinfunction "2_2") (pintype "input"))
      (node (ref "U2") (pin "6") (pinfunction "6_6") (pintype "input"))
    )
    (net (code "39") (name "unconnected-(U1-3V3-Pad17)") (class "Default")
      (node (ref "U1") (pin "17") (pinfunction "3V3_17") (pintype "input"))
    )
    (net (code "40") (name "unconnected-(U1-A6-Pad25)") (class "Default")
      (node (ref "U1") (pin "25") (pinfunction "A6_25") (pintype "input"))
    )
    (net (code "41") (name "unconnected-(U1-A7-Pad26)") (class "Default")
      (node (ref "U1") (pin "26") (pinfunction "A7_26") (pintype "input"))
    )
    (net (code "42") (name "unconnected-(U1-AREF-Pad18)") (class "Default")
      (node (ref "U1") (pin "18") (pinfunction "AREF_18") (pintype "input"))
    )
    (net (code "43") (name "unconnected-(U1-D0{slash}RX-Pad2)") (class "Default")
      (node (ref "U1") (pin "2") (pinfunction "D0/RX_2") (pintype "input"))
    )
    (net (code "44") (name "unconnected-(U1-D1{slash}TX-Pad1)") (class "Default")
      (node (ref "U1") (pin "1") (pinfunction "D1/TX_1") (pintype "input"))
    )
    (net (code "45") (name "unconnected-(U1-RESET-Pad3)") (class "Default")
      (node (ref "U1") (pin "3") (pinfunction "RESET_3") (pintype "input"))
    )
    (net (code "46") (name "unconnected-(U2-Pad10)") (class "Default")
      (node (ref "U2") (pin "10") (pinfunction "10_10") (pintype "input"))
    )
    (net (code "47") (name "unconnected-(U8-VREF-Pad5)") (class "Default")
      (node (ref "U8") (pin "5") (pinfunction "VREF_5") (pintype "input"))
    )
    (net (code "48") (name "unconnected-(U10-GND-Pad2)") (class "Default")
      (node (ref "U10") (pin "2") (pinfunction "GND_2") (pintype "input"))
    )
    (net (code "49") (name "unconnected-(U10-GND-Pad4)") (class "Default")
      (node (ref "U10") (pin "4") (pinfunction "GND_4") (pintype "input"))
    )
    (net (code "50") (name "unconnected-(U11-CLKOUT{slash}SOF-Pad3)") (class "Default")
      (node (ref "U11") (pin "3") (pinfunction "CLKOUT/SOF_3") (pintype "input"))
    )
    (net (code "51") (name "unconnected-(U11-RX0BF#-Pad11)") (class "Default")
      (node (ref "U11") (pin "11") (pinfunction "RX0BF#_11") (pintype "input"))
    )
    (net (code "52") (name "unconnected-(U11-RX1BF#-Pad10)") (class "Default")
      (node (ref "U11") (pin "10") (pinfunction "RX1BF#_10") (pintype "input"))
    )
    (net (code "53") (name "unconnected-(U11-TX0RTS#-Pad4)") (class "Default")
      (node (ref "U11") (pin "4") (pinfunction "TX0RTS#_4") (pintype "input"))
    )
    (net (code "54") (name "unconnected-(U11-TX1RTS#-Pad5)") (class "Default")
      (node (ref "U11") (pin "5") (pinfunction "TX1RTS#_5") (pintype "input"))
    )
    (net (code "55") (name "unconnected-(U11-TX2RTS#-Pad6)") (class "Default")
      (node (ref "U11") (pin "6") (pinfunction "TX2RTS#_6") (pintype "input"))
    )
    (net (code "56") (name "unconnected-(U12-n.c-Pad25)") (class "Default")
      (node (ref "U12") (pin "25") (pinfunction "n.c_25") (pintype "unspecified"))
    )
    (net (code "57") (name "unconnected-(U12-n.c.-Pad9)") (class "Default")
      (node (ref "U12") (pin "9") (pinfunction "n.c._9") (pintype "unspecified"))
    )
    (net (code "58") (name "unconnected-(U12-n.c.-Pad17)") (class "Default")
      (node (ref "U12") (pin "17") (pinfunction "n.c._17") (pintype "unspecified"))
    )
  )
)
